# SCH_usbhubSG_2024-06-20.net
KiCad netlist of a schematic drawn in EasyEDA
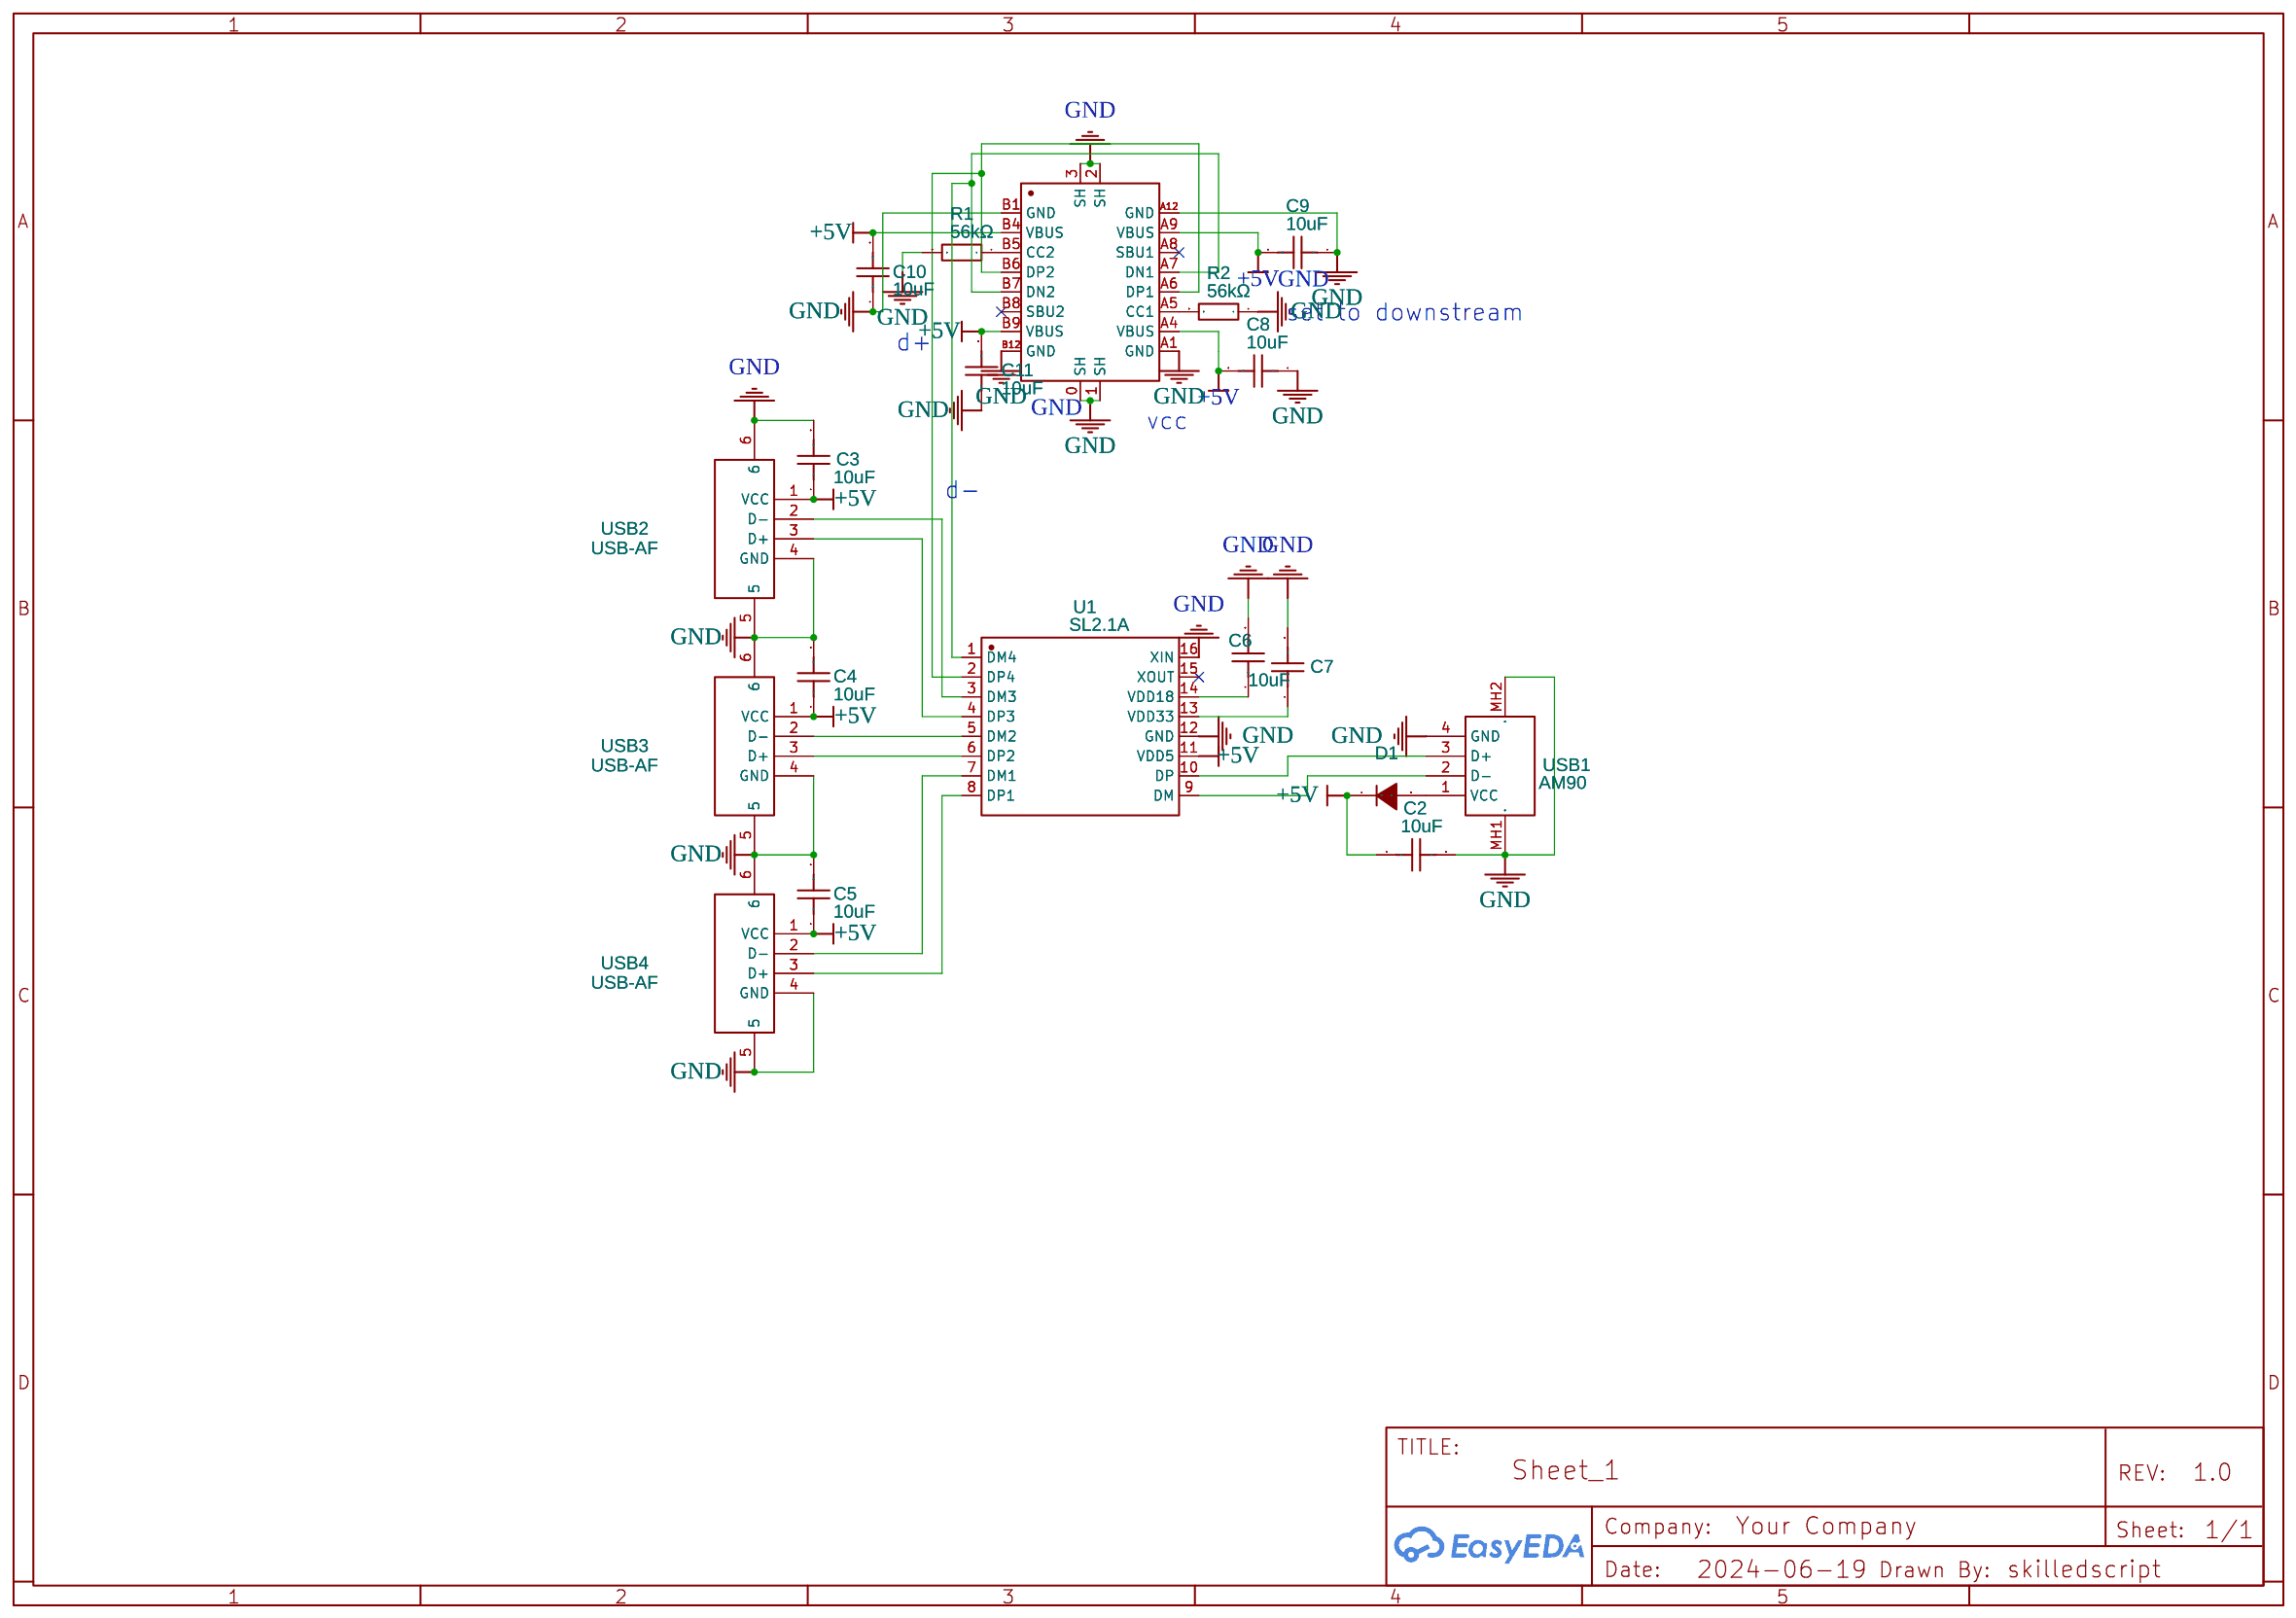
[diagram p0: schematic sheet]

(export (version "E")
  (design (tool "Eeschema 10.0.6"))
  (components
    (comp (ref "C2")
      (value "10uF")
      (fields
        (field (name "Manufacturer Part") "CL10A106KP8NNNC")
        (field (name "Manufacturer") "SAMSUNG(三星)")
      )
      (libsource (lib "") (part "CL10A106KP8NNNC_1"))
    )
    (comp (ref "C3")
      (value "10uF")
      (fields
        (field (name "Manufacturer Part") "CL10A106KP8NNNC")
        (field (name "Manufacturer") "SAMSUNG(三星)")
      )
      (libsource (lib "") (part "CL10A106KP8NNNC"))
    )
    (comp (ref "C4")
      (value "10uF")
      (fields
        (field (name "Manufacturer Part") "CL10A106KP8NNNC")
        (field (name "Manufacturer") "SAMSUNG(三星)")
      )
      (libsource (lib "") (part "CL10A106KP8NNNC"))
    )
    (comp (ref "C5")
      (value "10uF")
      (fields
        (field (name "Manufacturer Part") "CL10A106KP8NNNC")
        (field (name "Manufacturer") "SAMSUNG(三星)")
      )
      (libsource (lib "") (part "CL10A106KP8NNNC"))
    )
    (comp (ref "C6")
      (value "10uF")
      (fields
        (field (name "Manufacturer Part") "CL10A106KP8NNNC")
        (field (name "Manufacturer") "SAMSUNG(三星)")
      )
      (libsource (lib "") (part "CL10A106KP8NNNC"))
    )
    (comp (ref "C7")
      (value "10uF")
      (fields
        (field (name "Manufacturer Part") "CL10A106KP8NNNC")
        (field (name "Manufacturer") "SAMSUNG(三星)")
      )
      (libsource (lib "") (part "CL10A106KP8NNNC"))
    )
    (comp (ref "C8")
      (value "10uF")
      (fields
        (field (name "Manufacturer Part") "CL10A106KP8NNNC")
        (field (name "Manufacturer") "SAMSUNG(三星)")
      )
      (libsource (lib "") (part "CL10A106KP8NNNC_2"))
    )
    (comp (ref "C9")
      (value "10uF")
      (fields
        (field (name "Manufacturer Part") "CL10A106KP8NNNC")
        (field (name "Manufacturer") "SAMSUNG(三星)")
      )
      (libsource (lib "") (part "CL10A106KP8NNNC_2"))
    )
    (comp (ref "C10")
      (value "10uF")
      (fields
        (field (name "Manufacturer Part") "CL10A106KP8NNNC")
        (field (name "Manufacturer") "SAMSUNG(三星)")
      )
      (libsource (lib "") (part "CL10A106KP8NNNC"))
    )
    (comp (ref "C11")
      (value "10uF")
      (fields
        (field (name "Manufacturer Part") "CL10A106KP8NNNC")
        (field (name "Manufacturer") "SAMSUNG(三星)")
      )
      (libsource (lib "") (part "CL10A106KP8NNNC"))
    )
    (comp (ref "D1")
      (value "NSR0320MW2T1G")
      (fields (field (name "Manufacturer") "onsemi(安森美)"))
      (libsource (lib "") (part "NSR0320MW2T1G"))
    )
    (comp (ref "R1")
      (value "56kΩ")
      (fields (field (name "Manufacturer Part") "WR08X563JTL") (field (name "Manufacturer") "Walsin(华新科)"))
      (libsource (lib "") (part "WR08X563JTL"))
    )
    (comp (ref "R2")
      (value "56kΩ")
      (fields (field (name "Manufacturer Part") "WR08X563JTL") (field (name "Manufacturer") "Walsin(华新科)"))
      (libsource (lib "") (part "WR08X563JTL"))
    )
    (comp (ref "U1")
      (value "SL2.1A")
      (fields (field (name "Manufacturer") "CoreChips(和芯润德)"))
      (libsource (lib "") (part "SL2.1A"))
    )
    (comp (ref "USB1")
      (value "AM90")
      (fields (field (name "Manufacturer") "SHOU HAN(首韩)"))
      (libsource (lib "") (part "AM90"))
    )
    (comp (ref "USB2")
      (value "USB-AF")
      (fields (field (name "Manufacturer Part") "903-131A1011D10100") (field (name "Manufacturer") "精拓金"))
      (libsource (lib "") (part "USB-AF-90-14.4X13.6-H7.0-DIP"))
    )
    (comp (ref "USB3")
      (value "USB-AF")
      (fields (field (name "Manufacturer Part") "903-131A1011D10100") (field (name "Manufacturer") "精拓金"))
      (libsource (lib "") (part "USB-AF-90-14.4X13.6-H7.0-DIP"))
    )
    (comp (ref "USB4")
      (value "USB-AF")
      (fields (field (name "Manufacturer Part") "903-131A1011D10100") (field (name "Manufacturer") "精拓金"))
      (libsource (lib "") (part "USB-AF-90-14.4X13.6-H7.0-DIP"))
    )
    (comp (ref "USB5")
      (value "USB-TYPE-C-018")
      (fields (field (name "Manufacturer") "DEALON(德艺隆)"))
      (libsource (lib "") (part "USB-TYPE-C-018"))
    )
  )
  (nets
    (net (code "1") (name "+5V") (class "Default")
      (node (ref "C10") (pin "2") (pinfunction "2_2") (pintype "unspecified"))
      (node (ref "C11") (pin "2") (pinfunction "2_2") (pintype "unspecified"))
      (node (ref "C2") (pin "1") (pinfunction "1_1") (pintype "unspecified"))
      (node (ref "C3") (pin "1") (pinfunction "1_1") (pintype "unspecified"))
      (node (ref "C4") (pin "1") (pinfunction "1_1") (pintype "unspecified"))
      (node (ref "C5") (pin "1") (pinfunction "1_1") (pintype "unspecified"))
      (node (ref "C8") (pin "2") (pinfunction "2_2") (pintype "unspecified"))
      (node (ref "C9") (pin "2") (pinfunction "2_2") (pintype "unspecified"))
      (node (ref "D1") (pin "1") (pinfunction "C_1") (pintype "unspecified"))
      (node (ref "U1") (pin "11") (pinfunction "VDD5_11") (pintype "unspecified"))
      (node (ref "USB2") (pin "1") (pinfunction "VCC_1") (pintype "unspecified"))
      (node (ref "USB3") (pin "1") (pinfunction "VCC_1") (pintype "unspecified"))
      (node (ref "USB4") (pin "1") (pinfunction "VCC_1") (pintype "unspecified"))
      (node (ref "USB5") (pin "A4") (pinfunction "VBUS_A4") (pintype "unspecified"))
      (node (ref "USB5") (pin "A9") (pinfunction "VBUS_A9") (pintype "unspecified"))
      (node (ref "USB5") (pin "B4") (pinfunction "VBUS_B4") (pintype "unspecified"))
      (node (ref "USB5") (pin "B9") (pinfunction "VBUS_B9") (pintype "unspecified"))
    )
    (net (code "2") (name "GND") (class "Default")
      (node (ref "C10") (pin "1") (pinfunction "1_1") (pintype "unspecified"))
      (node (ref "C11") (pin "1") (pinfunction "1_1") (pintype "unspecified"))
      (node (ref "C2") (pin "2") (pinfunction "2_2") (pintype "unspecified"))
      (node (ref "C3") (pin "2") (pinfunction "2_2") (pintype "unspecified"))
      (node (ref "C4") (pin "2") (pinfunction "2_2") (pintype "unspecified"))
      (node (ref "C5") (pin "2") (pinfunction "2_2") (pintype "unspecified"))
      (node (ref "C6") (pin "2") (pinfunction "2_2") (pintype "unspecified"))
      (node (ref "C7") (pin "2") (pinfunction "2_2") (pintype "unspecified"))
      (node (ref "C8") (pin "1") (pinfunction "1_1") (pintype "unspecified"))
      (node (ref "C9") (pin "1") (pinfunction "1_1") (pintype "unspecified"))
      (node (ref "R1") (pin "2") (pinfunction "2_2") (pintype "unspecified"))
      (node (ref "R2") (pin "1") (pinfunction "1_1") (pintype "unspecified"))
      (node (ref "U1") (pin "12") (pinfunction "GND_12") (pintype "unspecified"))
      (node (ref "U1") (pin "16") (pinfunction "XIN_16") (pintype "unspecified"))
      (node (ref "USB1") (pin "4") (pinfunction "GND_4") (pintype "input"))
      (node (ref "USB1") (pin "MH1") (pinfunction "MH1_MH1") (pintype "unspecified"))
      (node (ref "USB1") (pin "MH2") (pinfunction "MH2_MH2") (pintype "unspecified"))
      (node (ref "USB2") (pin "4") (pinfunction "GND_4") (pintype "unspecified"))
      (node (ref "USB2") (pin "5") (pinfunction "5_5") (pintype "unspecified"))
      (node (ref "USB2") (pin "6") (pinfunction "6_6") (pintype "unspecified"))
      (node (ref "USB3") (pin "4") (pinfunction "GND_4") (pintype "unspecified"))
      (node (ref "USB3") (pin "5") (pinfunction "5_5") (pintype "unspecified"))
      (node (ref "USB3") (pin "6") (pinfunction "6_6") (pintype "unspecified"))
      (node (ref "USB4") (pin "4") (pinfunction "GND_4") (pintype "unspecified"))
      (node (ref "USB4") (pin "5") (pinfunction "5_5") (pintype "unspecified"))
      (node (ref "USB4") (pin "6") (pinfunction "6_6") (pintype "unspecified"))
      (node (ref "USB5") (pin "0") (pinfunction "SH_0") (pintype "unspecified"))
      (node (ref "USB5") (pin "1") (pinfunction "SH_1") (pintype "unspecified"))
      (node (ref "USB5") (pin "2") (pinfunction "SH_2") (pintype "unspecified"))
      (node (ref "USB5") (pin "3") (pinfunction "SH_3") (pintype "unspecified"))
      (node (ref "USB5") (pin "A1") (pinfunction "GND_A1") (pintype "unspecified"))
      (node (ref "USB5") (pin "A12") (pinfunction "GND_A12") (pintype "unspecified"))
      (node (ref "USB5") (pin "B1") (pinfunction "GND_B1") (pintype "unspecified"))
      (node (ref "USB5") (pin "B12") (pinfunction "GND_B12") (pintype "unspecified"))
    )
    (net (code "3") (name "Net-(D1-A)") (class "Default")
      (node (ref "D1") (pin "2") (pinfunction "A_2") (pintype "unspecified"))
      (node (ref "USB1") (pin "1") (pinfunction "VCC_1") (pintype "input"))
    )
    (net (code "4") (name "Net-(U1-DM)") (class "Default")
      (node (ref "U1") (pin "9") (pinfunction "DM_9") (pintype "unspecified"))
      (node (ref "USB1") (pin "2") (pinfunction "D-_2") (pintype "input"))
    )
    (net (code "5") (name "Net-(U1-DM1)") (class "Default")
      (node (ref "U1") (pin "7") (pinfunction "DM1_7") (pintype "unspecified"))
      (node (ref "USB4") (pin "2") (pinfunction "D-_2") (pintype "unspecified"))
    )
    (net (code "6") (name "Net-(U1-DM2)") (class "Default")
      (node (ref "U1") (pin "5") (pinfunction "DM2_5") (pintype "unspecified"))
      (node (ref "USB3") (pin "2") (pinfunction "D-_2") (pintype "unspecified"))
    )
    (net (code "7") (name "Net-(U1-DM3)") (class "Default")
      (node (ref "U1") (pin "3") (pinfunction "DM3_3") (pintype "unspecified"))
      (node (ref "USB2") (pin "2") (pinfunction "D-_2") (pintype "unspecified"))
    )
    (net (code "8") (name "Net-(U1-DM4)") (class "Default")
      (node (ref "U1") (pin "1") (pinfunction "DM4_1") (pintype "unspecified"))
      (node (ref "USB5") (pin "A7") (pinfunction "DN1_A7") (pintype "unspecified"))
      (node (ref "USB5") (pin "B7") (pinfunction "DN2_B7") (pintype "unspecified"))
    )
    (net (code "9") (name "Net-(U1-DP)") (class "Default")
      (node (ref "U1") (pin "10") (pinfunction "DP_10") (pintype "unspecified"))
      (node (ref "USB1") (pin "3") (pinfunction "D+_3") (pintype "input"))
    )
    (net (code "10") (name "Net-(U1-DP1)") (class "Default")
      (node (ref "U1") (pin "8") (pinfunction "DP1_8") (pintype "unspecified"))
      (node (ref "USB4") (pin "3") (pinfunction "D+_3") (pintype "unspecified"))
    )
    (net (code "11") (name "Net-(U1-DP2)") (class "Default")
      (node (ref "U1") (pin "6") (pinfunction "DP2_6") (pintype "unspecified"))
      (node (ref "USB3") (pin "3") (pinfunction "D+_3") (pintype "unspecified"))
    )
    (net (code "12") (name "Net-(U1-DP3)") (class "Default")
      (node (ref "U1") (pin "4") (pinfunction "DP3_4") (pintype "unspecified"))
      (node (ref "USB2") (pin "3") (pinfunction "D+_3") (pintype "unspecified"))
    )
    (net (code "13") (name "Net-(U1-DP4)") (class "Default")
      (node (ref "U1") (pin "2") (pinfunction "DP4_2") (pintype "unspecified"))
      (node (ref "USB5") (pin "A6") (pinfunction "DP1_A6") (pintype "unspecified"))
      (node (ref "USB5") (pin "B6") (pinfunction "DP2_B6") (pintype "unspecified"))
    )
    (net (code "14") (name "Net-(U1-VDD18)") (class "Default")
      (node (ref "C6") (pin "1") (pinfunction "1_1") (pintype "unspecified"))
      (node (ref "U1") (pin "14") (pinfunction "VDD18_14") (pintype "unspecified"))
    )
    (net (code "15") (name "Net-(U1-VDD33)") (class "Default")
      (node (ref "C7") (pin "1") (pinfunction "1_1") (pintype "unspecified"))
      (node (ref "U1") (pin "13") (pinfunction "VDD33_13") (pintype "unspecified"))
    )
    (net (code "16") (name "Net-(USB5-CC1)") (class "Default")
      (node (ref "R2") (pin "2") (pinfunction "2_2") (pintype "unspecified"))
      (node (ref "USB5") (pin "A5") (pinfunction "CC1_A5") (pintype "unspecified"))
    )
    (net (code "17") (name "Net-(USB5-CC2)") (class "Default")
      (node (ref "R1") (pin "1") (pinfunction "1_1") (pintype "unspecified"))
      (node (ref "USB5") (pin "B5") (pinfunction "CC2_B5") (pintype "unspecified"))
    )
    (net (code "18") (name "unconnected-(U1-XOUT-Pad15)") (class "Default")
      (node (ref "U1") (pin "15") (pinfunction "XOUT_15") (pintype "unspecified+no_connect"))
    )
    (net (code "19") (name "unconnected-(USB5-SBU1-PadA8)") (class "Default")
      (node (ref "USB5") (pin "A8") (pinfunction "SBU1_A8") (pintype "unspecified+no_connect"))
    )
    (net (code "20") (name "unconnected-(USB5-SBU2-PadB8)") (class "Default")
      (node (ref "USB5") (pin "B8") (pinfunction "SBU2_B8") (pintype "unspecified+no_connect"))
    )
  )
)
